# binary_watch.net
KiCad netlist of a schematic drawn in EasyEDA Pro
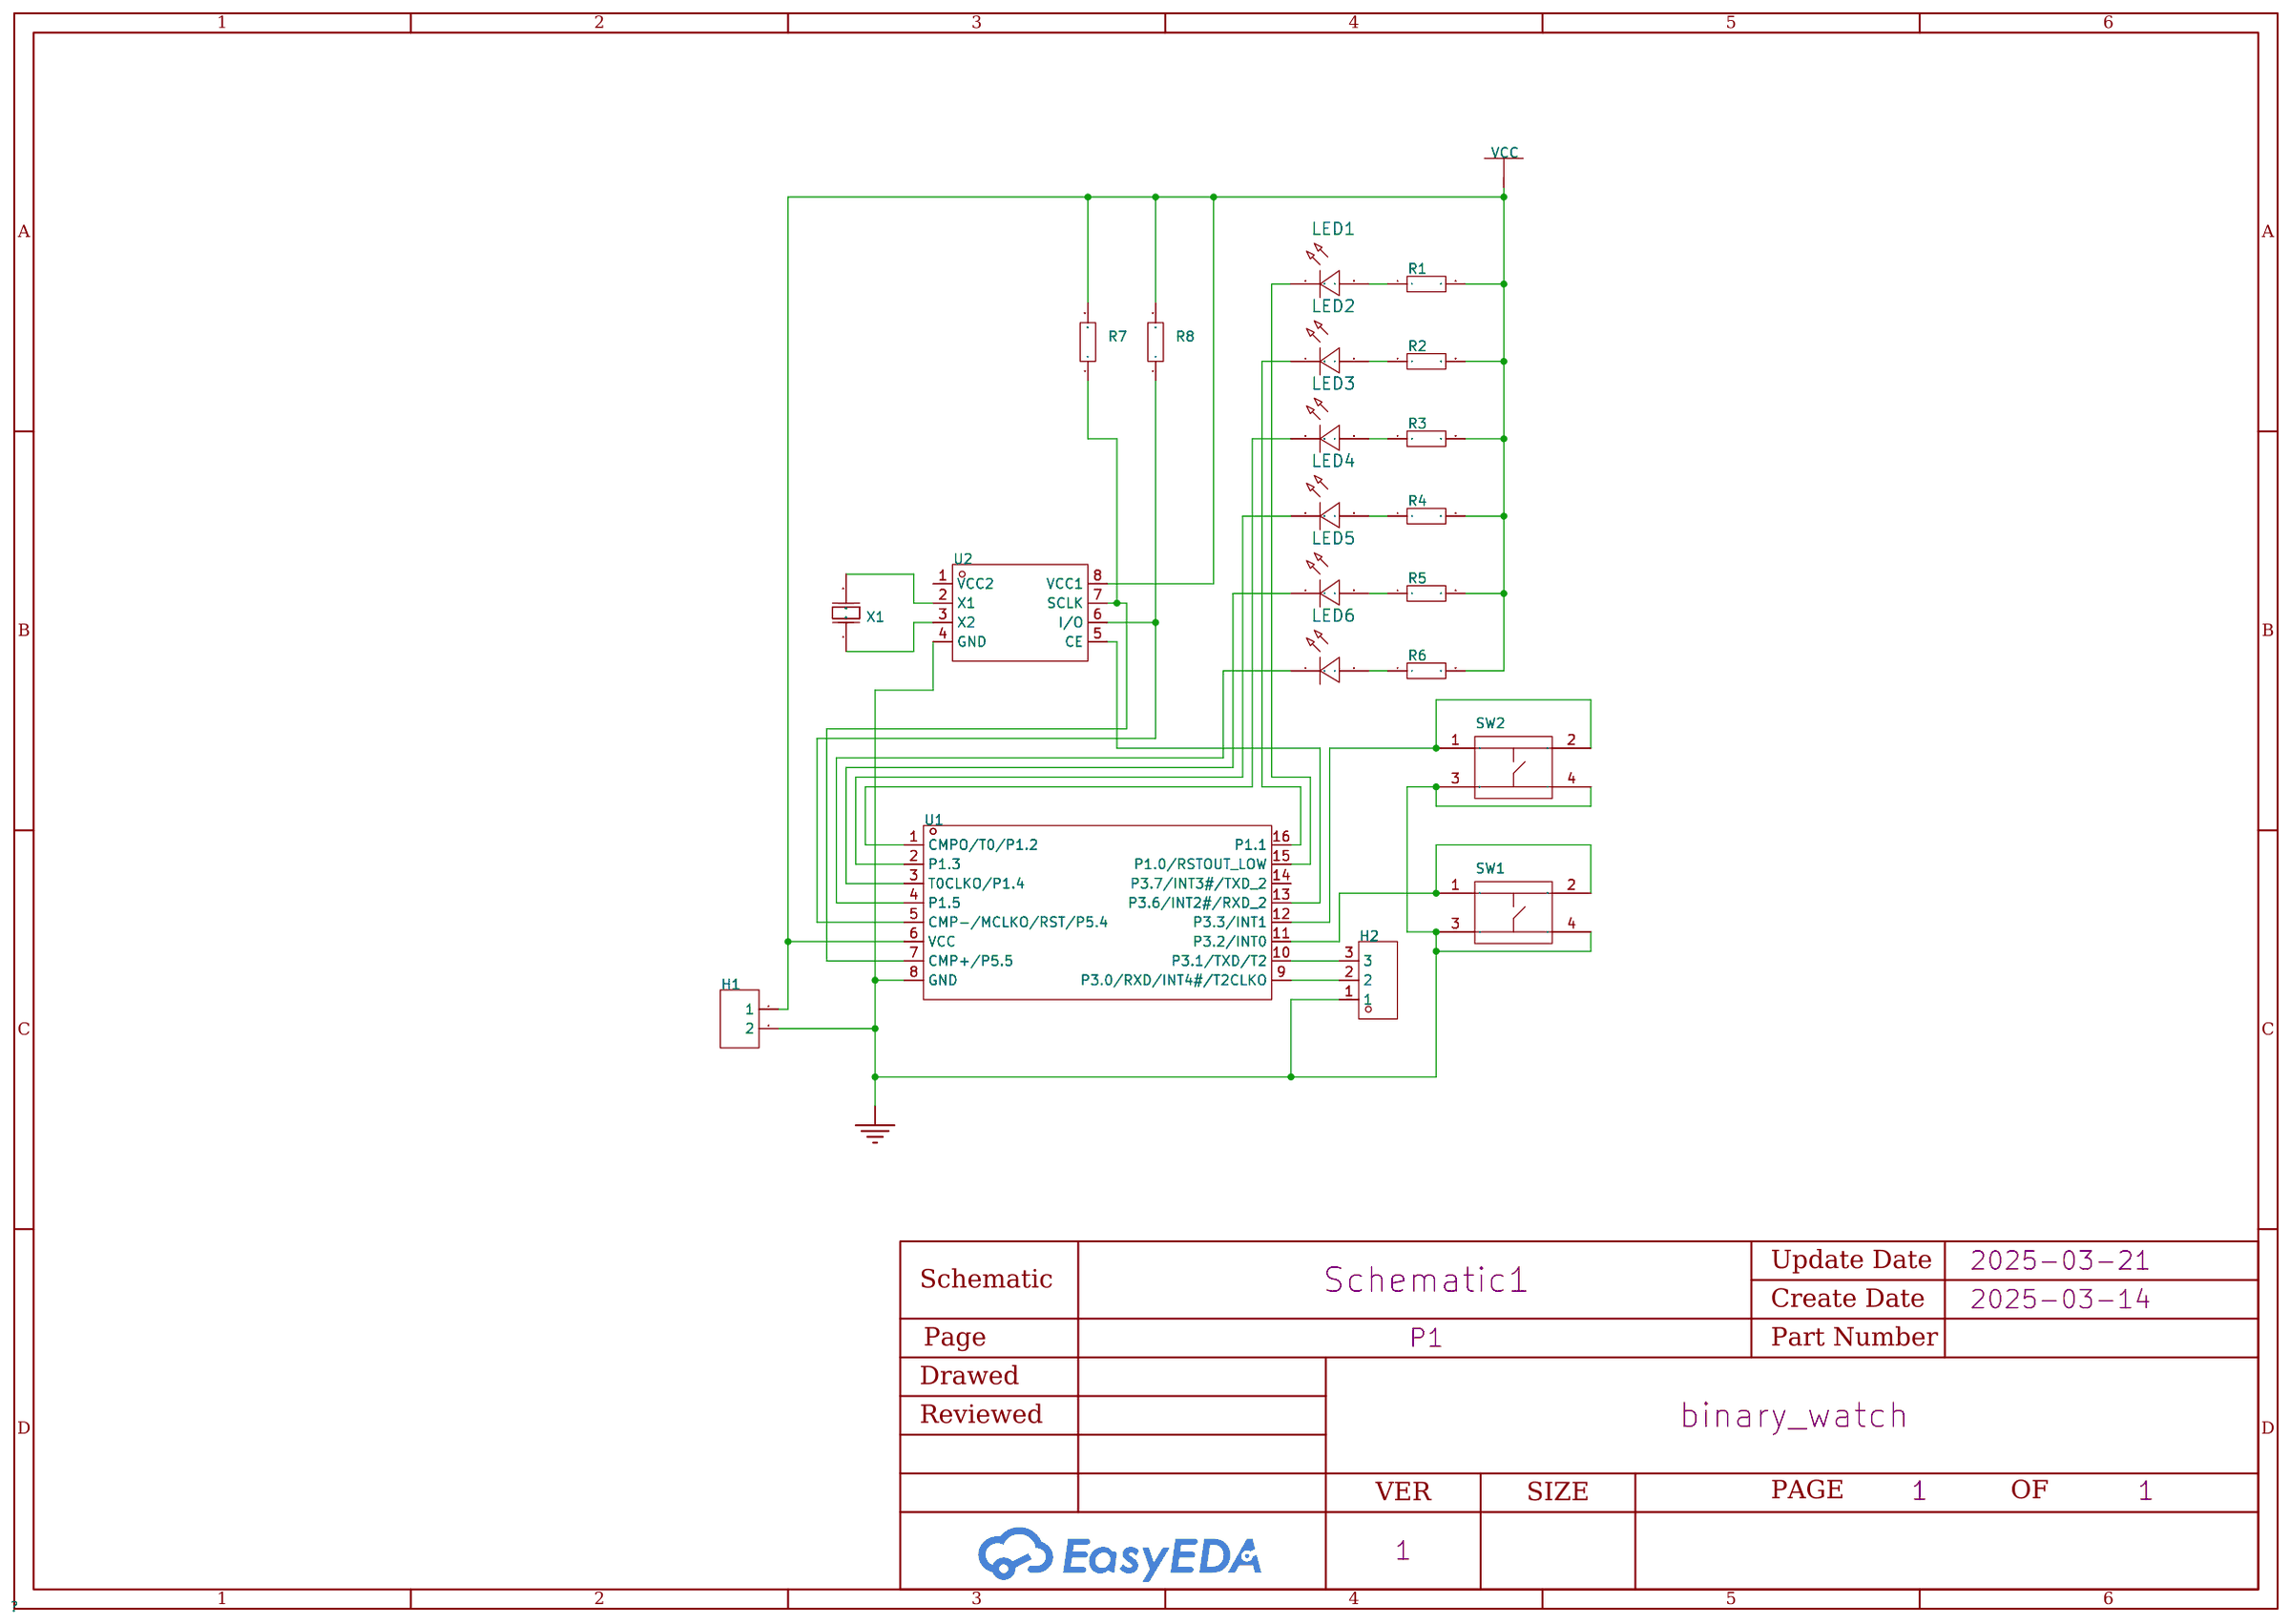
[diagram p0: schematic sheet]

(export (version "E")
  (design (tool "Eeschema 10.0.6"))
  (components
    (comp (ref "H1")
      (value "~")
      (footprint "easyedapro:HDR-TH_2P-P2.54-V-F")
      (libsource (lib "easyedapro") (part "Header-Female-2.54_1x2"))
    )
    (comp (ref "H2")
      (value "~")
      (footprint "easyedapro:HDR-TH_3P-P2.54-V-M")
      (libsource (lib "easyedapro") (part "PZ254V-11-03P_C2937625"))
    )
    (comp (ref "LED1")
      (value "~")
      (footprint "easyedapro:LED_0805")
      (libsource (lib "easyedapro") (part "LED_R"))
    )
    (comp (ref "LED2")
      (value "~")
      (footprint "easyedapro:LED_0805")
      (libsource (lib "easyedapro") (part "LED_R"))
    )
    (comp (ref "LED3")
      (value "~")
      (footprint "easyedapro:LED_0805")
      (libsource (lib "easyedapro") (part "LED_R"))
    )
    (comp (ref "LED4")
      (value "~")
      (footprint "easyedapro:LED_0805")
      (libsource (lib "easyedapro") (part "LED_R"))
    )
    (comp (ref "LED5")
      (value "~")
      (footprint "easyedapro:LED_0805")
      (libsource (lib "easyedapro") (part "LED_R"))
    )
    (comp (ref "LED6")
      (value "~")
      (footprint "easyedapro:LED_0805")
      (libsource (lib "easyedapro") (part "LED_R"))
    )
    (comp (ref "R1")
      (value "100Ω")
      (footprint "easyedapro:R0805")
      (fields (field (name "Manufacturer Part") "RS-05K1000FT") (field (name "Manufacturer") "FH(风华)"))
      (libsource (lib "easyedapro") (part "RS-05K1000FT"))
    )
    (comp (ref "R2")
      (value "100Ω")
      (footprint "easyedapro:R0805")
      (fields (field (name "Manufacturer Part") "RS-05K1000FT") (field (name "Manufacturer") "FH(风华)"))
      (libsource (lib "easyedapro") (part "RS-05K1000FT"))
    )
    (comp (ref "R3")
      (value "100Ω")
      (footprint "easyedapro:R0805")
      (fields (field (name "Manufacturer Part") "RS-05K1000FT") (field (name "Manufacturer") "FH(风华)"))
      (libsource (lib "easyedapro") (part "RS-05K1000FT"))
    )
    (comp (ref "R4")
      (value "100Ω")
      (footprint "easyedapro:R0805")
      (fields (field (name "Manufacturer Part") "RS-05K1000FT") (field (name "Manufacturer") "FH(风华)"))
      (libsource (lib "easyedapro") (part "RS-05K1000FT"))
    )
    (comp (ref "R5")
      (value "100Ω")
      (footprint "easyedapro:R0805")
      (fields (field (name "Manufacturer Part") "RS-05K1000FT") (field (name "Manufacturer") "FH(风华)"))
      (libsource (lib "easyedapro") (part "RS-05K1000FT"))
    )
    (comp (ref "R6")
      (value "100Ω")
      (footprint "easyedapro:R0805")
      (fields (field (name "Manufacturer Part") "RS-05K1000FT") (field (name "Manufacturer") "FH(风华)"))
      (libsource (lib "easyedapro") (part "RS-05K1000FT"))
    )
    (comp (ref "R7")
      (value "100Ω")
      (footprint "easyedapro:R0805")
      (fields (field (name "Manufacturer Part") "RS-05K1000FT") (field (name "Manufacturer") "FH(风华)"))
      (libsource (lib "easyedapro") (part "RS-05K1000FT"))
    )
    (comp (ref "R8")
      (value "100Ω")
      (footprint "easyedapro:R0805")
      (fields (field (name "Manufacturer Part") "RS-05K1000FT") (field (name "Manufacturer") "FH(风华)"))
      (libsource (lib "easyedapro") (part "RS-05K1000FT"))
    )
    (comp (ref "SW1")
      (value "~")
      (footprint "easyedapro:KEY-TH_4P-L6.0-W6.0-P4.50-LS6.5")
      (fields (field (name "Manufacturer Part") "K2-1102DP-C4SW-04") (field (name "Manufacturer") "韩国韩荣"))
      (libsource (lib "easyedapro") (part "K2-1102DP-C4SW-04"))
    )
    (comp (ref "SW2")
      (value "~")
      (footprint "easyedapro:KEY-TH_4P-L6.0-W6.0-P4.50-LS6.5")
      (fields (field (name "Manufacturer Part") "K2-1102DP-C4SW-04") (field (name "Manufacturer") "韩国韩荣"))
      (libsource (lib "easyedapro") (part "K2-1102DP-C4SW-04"))
    )
    (comp (ref "U1")
      (value "~")
      (footprint "easyedapro:SOP-16_L10.0-W3.9-P1.27-LS6.0-BL")
      (fields (field (name "Manufacturer Part") "STC15W204S-35I-SOP16"))
      (libsource (lib "easyedapro") (part "STC15W204S-35I-SOP16"))
    )
    (comp (ref "U2")
      (value "~")
      (footprint "easyedapro:SOIC-8_L4.9-W3.9-P1.27-LS6.0-BL")
      (fields (field (name "Manufacturer Part") "DS1302Z+T&R") (field (name "Manufacturer") "MAXIM(美信)"))
      (libsource (lib "easyedapro") (part "DS1302ZN+"))
    )
    (comp (ref "X1")
      (value "32.768kHz")
      (footprint "easyedapro:OSC-TH_BD2.0-P0.70-D0.3")
      (fields
        (field (name "Manufacturer Part") "DT-26-32.768K 6pF 20PPM")
        (field (name "Manufacturer") "KDS大真空")
      )
      (libsource (lib "easyedapro") (part "DT-26-32.768K-6PF-20PPM"))
    )
  )
  (nets
    (net (code "1") (name "GND") (class "Default")
      (node (ref "H1") (pin "2") (pinfunction "2_2") (pintype "input"))
      (node (ref "H2") (pin "1") (pinfunction "1_1") (pintype "input"))
      (node (ref "SW1") (pin "3") (pinfunction "3_3") (pintype "input"))
      (node (ref "SW1") (pin "4") (pinfunction "4_4") (pintype "input"))
      (node (ref "SW2") (pin "3") (pinfunction "3_3") (pintype "input"))
      (node (ref "SW2") (pin "4") (pinfunction "4_4") (pintype "input"))
      (node (ref "U1") (pin "8") (pinfunction "GND_8") (pintype "input"))
      (node (ref "U2") (pin "4") (pinfunction "GND_4") (pintype "input"))
    )
    (net (code "2") (name "Net-(LED1-A)") (class "Default")
      (node (ref "LED1") (pin "2") (pinfunction "A_2") (pintype "input"))
      (node (ref "R1") (pin "1") (pinfunction "1_1") (pintype "input"))
    )
    (net (code "3") (name "Net-(LED1-C)") (class "Default")
      (node (ref "LED1") (pin "1") (pinfunction "C_1") (pintype "input"))
      (node (ref "U1") (pin "15") (pinfunction "P1.0/RSTOUT_LOW_15") (pintype "input"))
    )
    (net (code "4") (name "Net-(LED2-A)") (class "Default")
      (node (ref "LED2") (pin "2") (pinfunction "A_2") (pintype "input"))
      (node (ref "R2") (pin "1") (pinfunction "1_1") (pintype "input"))
    )
    (net (code "5") (name "Net-(LED2-C)") (class "Default")
      (node (ref "LED2") (pin "1") (pinfunction "C_1") (pintype "input"))
      (node (ref "U1") (pin "16") (pinfunction "P1.1_16") (pintype "input"))
    )
    (net (code "6") (name "Net-(LED3-A)") (class "Default")
      (node (ref "LED3") (pin "2") (pinfunction "A_2") (pintype "input"))
      (node (ref "R3") (pin "1") (pinfunction "1_1") (pintype "input"))
    )
    (net (code "7") (name "Net-(LED3-C)") (class "Default")
      (node (ref "LED3") (pin "1") (pinfunction "C_1") (pintype "input"))
      (node (ref "U1") (pin "1") (pinfunction "CMPO/T0/P1.2_1") (pintype "input"))
    )
    (net (code "8") (name "Net-(LED4-A)") (class "Default")
      (node (ref "LED4") (pin "2") (pinfunction "A_2") (pintype "input"))
      (node (ref "R4") (pin "1") (pinfunction "1_1") (pintype "input"))
    )
    (net (code "9") (name "Net-(LED4-C)") (class "Default")
      (node (ref "LED4") (pin "1") (pinfunction "C_1") (pintype "input"))
      (node (ref "U1") (pin "2") (pinfunction "P1.3_2") (pintype "input"))
    )
    (net (code "10") (name "Net-(LED5-A)") (class "Default")
      (node (ref "LED5") (pin "2") (pinfunction "A_2") (pintype "input"))
      (node (ref "R5") (pin "1") (pinfunction "1_1") (pintype "input"))
    )
    (net (code "11") (name "Net-(LED5-C)") (class "Default")
      (node (ref "LED5") (pin "1") (pinfunction "C_1") (pintype "input"))
      (node (ref "U1") (pin "3") (pinfunction "T0CLKO/P1.4_3") (pintype "input"))
    )
    (net (code "12") (name "Net-(LED6-A)") (class "Default")
      (node (ref "LED6") (pin "2") (pinfunction "A_2") (pintype "input"))
      (node (ref "R6") (pin "1") (pinfunction "1_1") (pintype "input"))
    )
    (net (code "13") (name "Net-(LED6-C)") (class "Default")
      (node (ref "LED6") (pin "1") (pinfunction "C_1") (pintype "input"))
      (node (ref "U1") (pin "4") (pinfunction "P1.5_4") (pintype "input"))
    )
    (net (code "14") (name "Net-(U1-CMP+{slash}P5.5)") (class "Default")
      (node (ref "R7") (pin "1") (pinfunction "1_1") (pintype "input"))
      (node (ref "U1") (pin "7") (pinfunction "CMP+/P5.5_7") (pintype "input"))
      (node (ref "U2") (pin "7") (pinfunction "SCLK_7") (pintype "input"))
    )
    (net (code "15") (name "Net-(U1-CMP-{slash}MCLKO{slash}RST{slash}P5.4)") (class "Default")
      (node (ref "R8") (pin "1") (pinfunction "1_1") (pintype "input"))
      (node (ref "U1") (pin "5") (pinfunction "CMP-/MCLKO/RST/P5.4_5") (pintype "input"))
      (node (ref "U2") (pin "6") (pinfunction "I/O_6") (pintype "input"))
    )
    (net (code "16") (name "Net-(U1-P3.0{slash}RXD{slash}INT4#{slash}T2CLKO)") (class "Default")
      (node (ref "H2") (pin "2") (pinfunction "2_2") (pintype "input"))
      (node (ref "U1") (pin "9") (pinfunction "P3.0/RXD/INT4#/T2CLKO_9") (pintype "input"))
    )
    (net (code "17") (name "Net-(U1-P3.1{slash}TXD{slash}T2)") (class "Default")
      (node (ref "H2") (pin "3") (pinfunction "3_3") (pintype "input"))
      (node (ref "U1") (pin "10") (pinfunction "P3.1/TXD/T2_10") (pintype "input"))
    )
    (net (code "18") (name "Net-(U1-P3.2{slash}INT0)") (class "Default")
      (node (ref "SW1") (pin "1") (pinfunction "1_1") (pintype "input"))
      (node (ref "SW1") (pin "2") (pinfunction "2_2") (pintype "input"))
      (node (ref "U1") (pin "11") (pinfunction "P3.2/INT0_11") (pintype "input"))
    )
    (net (code "19") (name "Net-(U1-P3.3{slash}INT1)") (class "Default")
      (node (ref "SW2") (pin "1") (pinfunction "1_1") (pintype "input"))
      (node (ref "SW2") (pin "2") (pinfunction "2_2") (pintype "input"))
      (node (ref "U1") (pin "12") (pinfunction "P3.3/INT1_12") (pintype "input"))
    )
    (net (code "20") (name "Net-(U1-P3.6{slash}INT2#{slash}RXD_2)") (class "Default")
      (node (ref "U1") (pin "13") (pinfunction "P3.6/INT2#/RXD_2_13") (pintype "input"))
      (node (ref "U2") (pin "5") (pinfunction "CE_5") (pintype "input"))
    )
    (net (code "21") (name "Net-(U2-X1)") (class "Default")
      (node (ref "U2") (pin "2") (pinfunction "X1_2") (pintype "input"))
      (node (ref "X1") (pin "2") (pinfunction "OSC2_2") (pintype "input"))
    )
    (net (code "22") (name "Net-(U2-X2)") (class "Default")
      (node (ref "U2") (pin "3") (pinfunction "X2_3") (pintype "input"))
      (node (ref "X1") (pin "1") (pinfunction "OSC1_1") (pintype "input"))
    )
    (net (code "23") (name "VCC") (class "Default")
      (node (ref "H1") (pin "1") (pinfunction "1_1") (pintype "input"))
      (node (ref "R1") (pin "2") (pinfunction "2_2") (pintype "input"))
      (node (ref "R2") (pin "2") (pinfunction "2_2") (pintype "input"))
      (node (ref "R3") (pin "2") (pinfunction "2_2") (pintype "input"))
      (node (ref "R4") (pin "2") (pinfunction "2_2") (pintype "input"))
      (node (ref "R5") (pin "2") (pinfunction "2_2") (pintype "input"))
      (node (ref "R6") (pin "2") (pinfunction "2_2") (pintype "input"))
      (node (ref "R7") (pin "2") (pinfunction "2_2") (pintype "input"))
      (node (ref "R8") (pin "2") (pinfunction "2_2") (pintype "input"))
      (node (ref "U1") (pin "6") (pinfunction "VCC_6") (pintype "input"))
      (node (ref "U2") (pin "8") (pinfunction "VCC1_8") (pintype "input"))
    )
    (net (code "24") (name "unconnected-(U1-P3.7{slash}INT3#{slash}TXD_2-Pad14)") (class "Default")
      (node (ref "U1") (pin "14") (pinfunction "P3.7/INT3#/TXD_2_14") (pintype "input"))
    )
    (net (code "25") (name "unconnected-(U2-VCC2-Pad1)") (class "Default")
      (node (ref "U2") (pin "1") (pinfunction "VCC2_1") (pintype "input"))
    )
  )
)
